# Power.net
KiCad netlist of a schematic drawn in Altium Designer
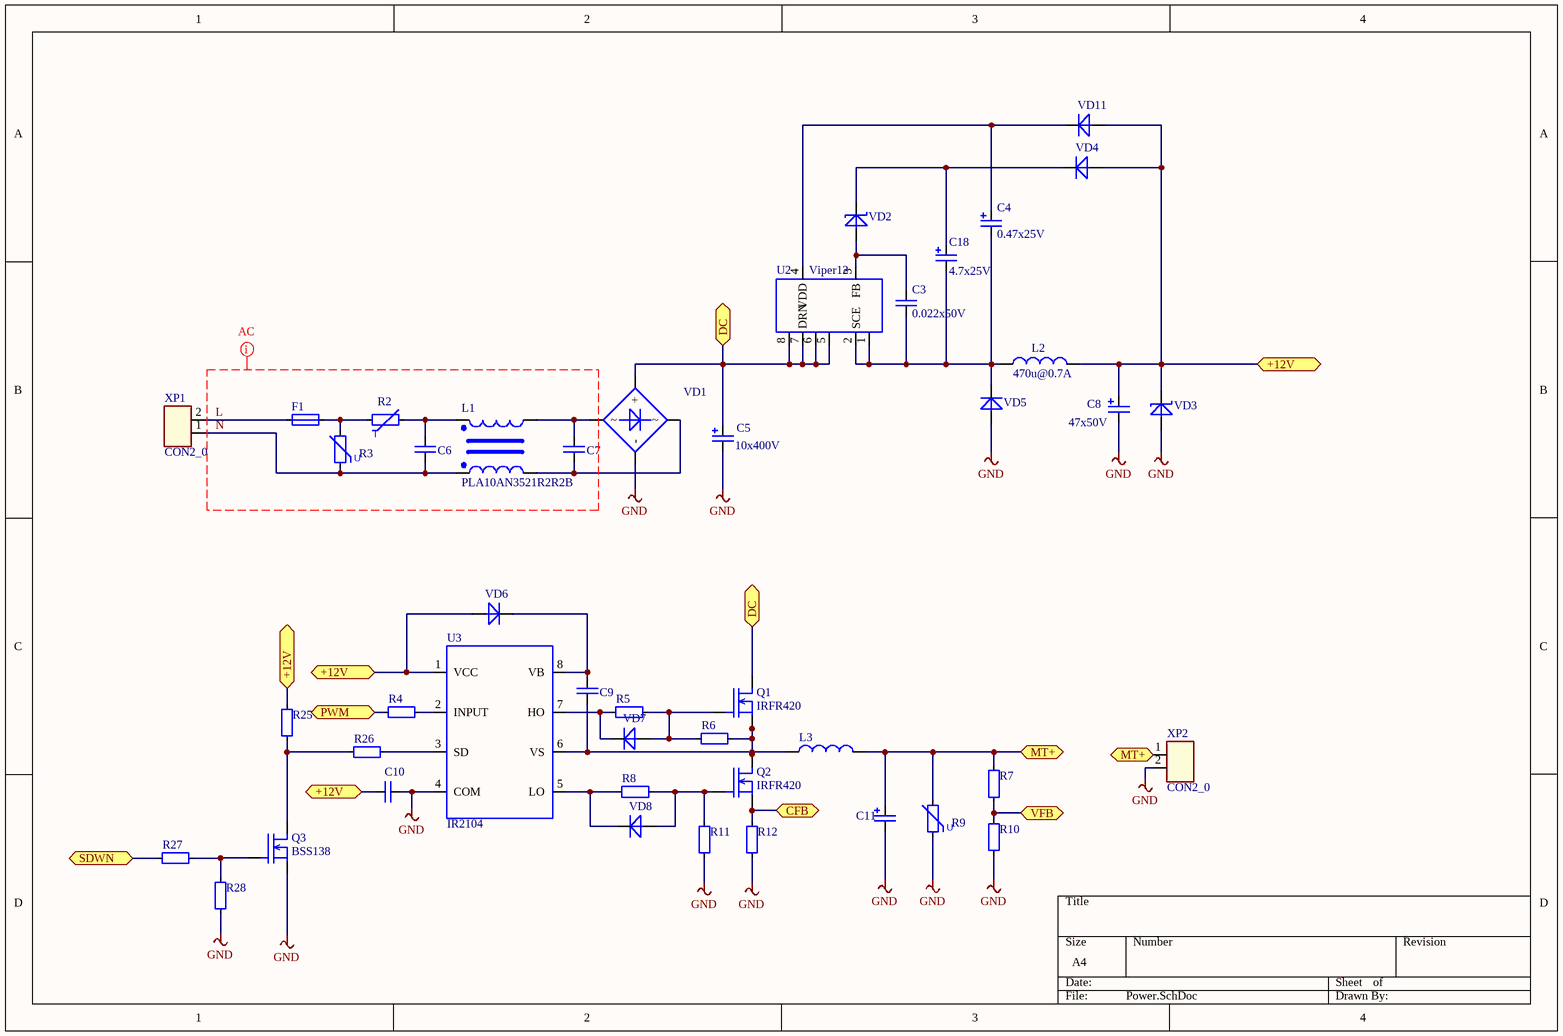
[diagram p0: Power.SchDoc]

(export (version "E")
  (design (tool "Eeschema 10.0.6"))
  (components
    (comp (ref "C3")
      (value "0.022x50V")
      (footprint "DISCRETE:SMD_0805")
      (description "None polar capacitor")
      (libsource (lib "DISCRETE") (part "C_NONE_POLAR"))
    )
    (comp (ref "C4")
      (value "0.47x25V")
      (footprint "DISCRETE:CAPR-5/2.5")
      (description "Polar capacitor")
      (libsource (lib "DISCRETE") (part "C_POLAR"))
    )
    (comp (ref "C5")
      (value "10x400V")
      (footprint "DISCRETE:CAPR-10/5")
      (description "Polar capacitor")
      (libsource (lib "DISCRETE") (part "C_POLAR"))
    )
    (comp (ref "C6")
      (value "~")
      (footprint "DISCRETE:MKR-X2-0.22-10")
      (description "None polar capacitor")
      (libsource (lib "DISCRETE") (part "C_NONE_POLAR"))
    )
    (comp (ref "C7")
      (value "~")
      (footprint "DISCRETE:MKR-X2-0.22-10")
      (description "None polar capacitor")
      (libsource (lib "DISCRETE") (part "C_NONE_POLAR"))
    )
    (comp (ref "C8")
      (value "47x50V")
      (footprint "DISCRETE:CAPR-5/2.5")
      (description "Polar capacitor")
      (libsource (lib "DISCRETE") (part "C_POLAR"))
    )
    (comp (ref "C9")
      (value "~")
      (footprint "DISCRETE:SMD_0805")
      (description "None polar capacitor")
      (libsource (lib "DISCRETE") (part "C_NONE_POLAR"))
    )
    (comp (ref "C10")
      (value "~")
      (footprint "DISCRETE:SMD_0805")
      (description "None polar capacitor")
      (libsource (lib "DISCRETE") (part "C_NONE_POLAR"))
    )
    (comp (ref "C11")
      (value "~")
      (footprint "DISCRETE:CAPR-5/2.5")
      (description "Polar capacitor")
      (libsource (lib "DISCRETE") (part "C_POLAR"))
    )
    (comp (ref "C18")
      (value "4.7x25V")
      (footprint "DISCRETE:CAPR-5/2.5")
      (description "Polar capacitor")
      (libsource (lib "DISCRETE") (part "C_POLAR"))
    )
    (comp (ref "F1")
      (value "~")
      (footprint "DISCRETE:KLS-1009")
      (description "Resistor")
      (libsource (lib "DISCRETE") (part "FUSE"))
    )
    (comp (ref "L1")
      (value "PLA10AN3521R2R2B")
      (footprint "DISCRETE:PLA10AN3521R2R2B")
      (libsource (lib "DISCRETE") (part "Inductor Sin"))
    )
    (comp (ref "L2")
      (value "470u@0.7A")
      (footprint "DISCRETE:IND-DV0470.00K")
      (libsource (lib "DISCRETE") (part "INDUCTOR"))
    )
    (comp (ref "L3")
      (value "~")
      (footprint "DISCRETE:IND-DV0470.00K")
      (libsource (lib "DISCRETE") (part "INDUCTOR"))
    )
    (comp (ref "Q1")
      (value "IRFR420")
      (footprint "DISCRETE:TO-252")
      (description "IG-FET N-Channel")
      (libsource (lib "Transistors") (part "IRFR420"))
    )
    (comp (ref "Q2")
      (value "IRFR420")
      (footprint "DISCRETE:TO-252")
      (description "IG-FET N-Channel")
      (libsource (lib "Transistors") (part "IRFR420"))
    )
    (comp (ref "Q3")
      (value "BSS138")
      (footprint "DISCRETE:SOT23-3PIN")
      (description "IG-FET N-Channel")
      (libsource (lib "Transistors") (part "BSS138"))
    )
    (comp (ref "R2")
      (value "RES NTC")
      (footprint "DISCRETE:NTC-5mm")
      (libsource (lib "DISCRETE") (part "RES NTC"))
    )
    (comp (ref "R3")
      (value "RES VARISTOR")
      (footprint "DISCRETE:VAR-10D")
      (libsource (lib "DISCRETE") (part "RES VARISTOR"))
    )
    (comp (ref "R4")
      (value "~")
      (footprint "DISCRETE:SMD_0805")
      (description "Resistor")
      (libsource (lib "DISCRETE") (part "RES"))
    )
    (comp (ref "R5")
      (value "~")
      (footprint "DISCRETE:SMD_0805")
      (description "Resistor")
      (libsource (lib "") (part "RES_2"))
    )
    (comp (ref "R6")
      (value "~")
      (footprint "DISCRETE:SMD_0805")
      (description "Resistor")
      (libsource (lib "DISCRETE") (part "RES"))
    )
    (comp (ref "R7")
      (value "~")
      (footprint "DISCRETE:SMD_0805")
      (description "Resistor")
      (libsource (lib "") (part "RES_3"))
    )
    (comp (ref "R8")
      (value "~")
      (footprint "DISCRETE:SMD_0805")
      (description "Resistor")
      (libsource (lib "") (part "RES_2"))
    )
    (comp (ref "R9")
      (value "RES VARISTOR")
      (footprint "DISCRETE:VAR-05D")
      (libsource (lib "DISCRETE") (part "RES VARISTOR"))
    )
    (comp (ref "R10")
      (value "~")
      (footprint "DISCRETE:SMD_0805")
      (description "Resistor")
      (libsource (lib "") (part "RES_3"))
    )
    (comp (ref "R11")
      (value "~")
      (footprint "DISCRETE:SMD_0805")
      (description "Resistor")
      (libsource (lib "") (part "RES_1"))
    )
    (comp (ref "R12")
      (value "~")
      (footprint "DISCRETE:SMD_0805")
      (description "Resistor")
      (libsource (lib "") (part "RES_1"))
    )
    (comp (ref "R25")
      (value "~")
      (footprint "DISCRETE:SMD_0805")
      (description "Resistor")
      (libsource (lib "") (part "RES_3"))
    )
    (comp (ref "R26")
      (value "~")
      (footprint "DISCRETE:SMD_0805")
      (description "Resistor")
      (libsource (lib "DISCRETE") (part "RES"))
    )
    (comp (ref "R27")
      (value "~")
      (footprint "DISCRETE:SMD_0805")
      (description "Resistor")
      (libsource (lib "") (part "RES_2"))
    )
    (comp (ref "R28")
      (value "~")
      (footprint "DISCRETE:SMD_0805")
      (description "Resistor")
      (libsource (lib "") (part "RES_3"))
    )
    (comp (ref "U2")
      (value "Viper12")
      (footprint "ICs:SO8-150mil")
      (description "Step-Down Converter")
      (fields (field (name "MANUFACTURER") "STMicro"))
      (libsource (lib "ICs") (part "Viper12"))
    )
    (comp (ref "U3") (value "IR2104") (footprint "ICs:SO8-150mil") (libsource (lib "ICs") (part "IR2104")))
    (comp (ref "VD1")
      (value "DIODE BRIDGE")
      (footprint "DISCRETE:GBU BRIDGE")
      (libsource (lib "DISCRETE") (part "DIODE BRIDGE"))
    )
    (comp (ref "VD2")
      (value "~")
      (footprint "DISCRETE:SOD-123")
      (description "Zener diode")
      (libsource (lib "DISCRETE") (part "ZENER"))
    )
    (comp (ref "VD3")
      (value "~")
      (footprint "DISCRETE:SOD-123")
      (description "Zener diode")
      (libsource (lib "DISCRETE") (part "ZENER"))
    )
    (comp (ref "VD4")
      (value "~")
      (footprint "DISCRETE:DO214-AC")
      (description "Diode")
      (libsource (lib "DISCRETE") (part "DIODE"))
    )
    (comp (ref "VD5")
      (value "~")
      (footprint "DISCRETE:DO214-AC")
      (description "Diode")
      (libsource (lib "DISCRETE") (part "DIODE"))
    )
    (comp (ref "VD6")
      (value "~")
      (footprint "DISCRETE:DO214-AC")
      (description "Diode")
      (libsource (lib "DISCRETE") (part "DIODE"))
    )
    (comp (ref "VD7")
      (value "~")
      (footprint "DISCRETE:DIO-MELF_SOD-80")
      (description "Diode")
      (libsource (lib "DISCRETE") (part "DIODE"))
    )
    (comp (ref "VD8")
      (value "~")
      (footprint "DISCRETE:DIO-MELF_SOD-80")
      (description "Diode")
      (libsource (lib "DISCRETE") (part "DIODE"))
    )
    (comp (ref "VD11")
      (value "~")
      (footprint "DISCRETE:DO214-AC")
      (description "Diode")
      (libsource (lib "DISCRETE") (part "DIODE"))
    )
    (comp (ref "XP1")
      (value "CON2_0")
      (footprint "Connectors:SCREW_TERM-5.0/2")
      (libsource (lib "Connectors") (part "CON2_0"))
    )
    (comp (ref "XP2")
      (value "CON2_0")
      (footprint "Connectors:SCREW_TERM-5.0/2")
      (libsource (lib "") (part "CON2_0_1"))
    )
  )
  (nets
    (net (code "1") (name "/+12V") (class "Default")
      (node (ref "C10") (pin "1") (pintype "passive"))
      (node (ref "C8") (pin "1") (pintype "passive"))
      (node (ref "L2") (pin "2") (pinfunction "2_2") (pintype "passive"))
      (node (ref "R25") (pin "2") (pintype "passive"))
      (node (ref "U3") (pin "1") (pinfunction "VCC_1") (pintype "passive"))
      (node (ref "VD11") (pin "2") (pinfunction "A_2") (pintype "passive"))
      (node (ref "VD3") (pin "1") (pinfunction "C_1") (pintype "passive"))
      (node (ref "VD4") (pin "2") (pinfunction "A_2") (pintype "passive"))
      (node (ref "VD6") (pin "2") (pinfunction "A_2") (pintype "passive"))
    )
    (net (code "2") (name "/CFB") (class "Default")
      (node (ref "Q2") (pin "3") (pinfunction "D_3") (pintype "passive"))
      (node (ref "R12") (pin "1") (pintype "passive"))
    )
    (net (code "3") (name "/DC") (class "Default")
      (node (ref "C5") (pin "1") (pintype "passive"))
      (node (ref "Q1") (pin "2") (pinfunction "S_2") (pintype "passive"))
      (node (ref "U2") (pin "5") (pinfunction "DRN_5") (pintype "passive"))
      (node (ref "U2") (pin "6") (pinfunction "DRN_6") (pintype "passive"))
      (node (ref "U2") (pin "7") (pinfunction "DRN_7") (pintype "passive"))
      (node (ref "U2") (pin "8") (pinfunction "DRN_8") (pintype "passive"))
      (node (ref "VD1") (pin "1") (pinfunction "+_1") (pintype "passive"))
    )
    (net (code "4") (name "/L") (class "Default")
      (node (ref "F1") (pin "2") (pintype "passive"))
      (node (ref "XP1") (pin "2") (pinfunction "2_2") (pintype "passive"))
    )
    (net (code "5") (name "/MT+") (class "Default")
      (node (ref "C11") (pin "1") (pintype "passive"))
      (node (ref "L3") (pin "2") (pinfunction "2_2") (pintype "passive"))
      (node (ref "R7") (pin "2") (pintype "passive"))
      (node (ref "R9") (pin "2") (pintype "passive"))
      (node (ref "XP2") (pin "1") (pinfunction "1_1") (pintype "passive"))
    )
    (net (code "6") (name "/N") (class "Default")
      (node (ref "C6") (pin "2") (pintype "passive"))
      (node (ref "L1") (pin "1") (pinfunction "1_1") (pintype "passive"))
      (node (ref "R3") (pin "1") (pintype "passive"))
      (node (ref "XP1") (pin "1") (pinfunction "1_1") (pintype "passive"))
    )
    (net (code "7") (name "/PWM") (class "Default") (node (ref "R4") (pin "1") (pintype "passive")))
    (net (code "8") (name "/SDWN") (class "Default") (node (ref "R27") (pin "2") (pintype "passive")))
    (net (code "9") (name "/VFB") (class "Default")
      (node (ref "R10") (pin "2") (pintype "passive"))
      (node (ref "R7") (pin "1") (pintype "passive"))
    )
    (net (code "10") (name "GND") (class "Default")
      (node (ref "C10") (pin "2") (pintype "passive"))
      (node (ref "C11") (pin "2") (pintype "passive"))
      (node (ref "C5") (pin "2") (pintype "passive"))
      (node (ref "C8") (pin "2") (pintype "passive"))
      (node (ref "Q3") (pin "2") (pinfunction "S_2") (pintype "passive"))
      (node (ref "R10") (pin "1") (pintype "passive"))
      (node (ref "R11") (pin "2") (pintype "passive"))
      (node (ref "R12") (pin "2") (pintype "passive"))
      (node (ref "R28") (pin "1") (pintype "passive"))
      (node (ref "R9") (pin "1") (pintype "passive"))
      (node (ref "U3") (pin "4") (pinfunction "COM_4") (pintype "passive"))
      (node (ref "VD1") (pin "4") (pinfunction "-_4") (pintype "passive"))
      (node (ref "VD3") (pin "2") (pinfunction "A_2") (pintype "passive"))
      (node (ref "VD5") (pin "2") (pinfunction "A_2") (pintype "passive"))
      (node (ref "XP2") (pin "2") (pinfunction "2_2") (pintype "passive"))
    )
    (net (code "11") (name "Net-(C6-Pad1)") (class "Default")
      (node (ref "C6") (pin "1") (pintype "passive"))
      (node (ref "L1") (pin "4") (pinfunction "4_4") (pintype "passive"))
      (node (ref "R2") (pin "2") (pintype "passive"))
    )
    (net (code "12") (name "Net-(C7-Pad1)") (class "Default")
      (node (ref "C7") (pin "1") (pintype "passive"))
      (node (ref "L1") (pin "3") (pinfunction "3_3") (pintype "passive"))
      (node (ref "VD1") (pin "2") (pinfunction "~_2") (pintype "passive"))
    )
    (net (code "13") (name "Net-(C7-Pad2)") (class "Default")
      (node (ref "C7") (pin "2") (pintype "passive"))
      (node (ref "L1") (pin "2") (pinfunction "2_2") (pintype "passive"))
      (node (ref "VD1") (pin "3") (pinfunction "~_3") (pintype "passive"))
    )
    (net (code "14") (name "Net-(F1-Pad1)") (class "Default")
      (node (ref "F1") (pin "1") (pintype "passive"))
      (node (ref "R2") (pin "1") (pintype "passive"))
      (node (ref "R3") (pin "2") (pintype "passive"))
    )
    (net (code "15") (name "Net-(Q1-D)") (class "Default")
      (node (ref "C9") (pin "2") (pintype "passive"))
      (node (ref "L3") (pin "1") (pinfunction "1_1") (pintype "passive"))
      (node (ref "Q1") (pin "3") (pinfunction "D_3") (pintype "passive"))
      (node (ref "Q2") (pin "2") (pinfunction "S_2") (pintype "passive"))
      (node (ref "R6") (pin "2") (pintype "passive"))
      (node (ref "U3") (pin "6") (pinfunction "VS_6") (pintype "passive"))
    )
    (net (code "16") (name "Net-(Q1-G)") (class "Default")
      (node (ref "Q1") (pin "1") (pinfunction "G_1") (pintype "passive"))
      (node (ref "R5") (pin "1") (pintype "passive"))
      (node (ref "R6") (pin "1") (pintype "passive"))
      (node (ref "VD7") (pin "2") (pinfunction "A_2") (pintype "passive"))
    )
    (net (code "17") (name "Net-(Q2-G)") (class "Default")
      (node (ref "Q2") (pin "1") (pinfunction "G_1") (pintype "passive"))
      (node (ref "R11") (pin "1") (pintype "passive"))
      (node (ref "R8") (pin "1") (pintype "passive"))
      (node (ref "VD8") (pin "2") (pinfunction "A_2") (pintype "passive"))
    )
    (net (code "18") (name "Net-(Q3-D)") (class "Default")
      (node (ref "Q3") (pin "3") (pinfunction "D_3") (pintype "passive"))
      (node (ref "R25") (pin "1") (pintype "passive"))
      (node (ref "R26") (pin "1") (pintype "passive"))
    )
    (net (code "19") (name "Net-(Q3-G)") (class "Default")
      (node (ref "Q3") (pin "1") (pinfunction "G_1") (pintype "passive"))
      (node (ref "R27") (pin "1") (pintype "passive"))
      (node (ref "R28") (pin "2") (pintype "passive"))
    )
    (net (code "20") (name "Net-(U2-FB)") (class "Default")
      (node (ref "C3") (pin "1") (pintype "passive"))
      (node (ref "U2") (pin "3") (pinfunction "FB_3") (pintype "passive"))
      (node (ref "VD2") (pin "2") (pinfunction "A_2") (pintype "passive"))
    )
    (net (code "21") (name "Net-(U2-VDD)") (class "Default")
      (node (ref "C4") (pin "1") (pintype "passive"))
      (node (ref "U2") (pin "4") (pinfunction "VDD_4") (pintype "passive"))
      (node (ref "VD11") (pin "1") (pinfunction "C_1") (pintype "passive"))
    )
    (net (code "22") (name "Net-(U3-HO)") (class "Default")
      (node (ref "R5") (pin "2") (pintype "passive"))
      (node (ref "U3") (pin "7") (pinfunction "HO_7") (pintype "passive"))
      (node (ref "VD7") (pin "1") (pinfunction "C_1") (pintype "passive"))
    )
    (net (code "23") (name "Net-(U3-INPUT)") (class "Default")
      (node (ref "R4") (pin "2") (pintype "passive"))
      (node (ref "U3") (pin "2") (pinfunction "INPUT_2") (pintype "passive"))
    )
    (net (code "24") (name "Net-(U3-LO)") (class "Default")
      (node (ref "R8") (pin "2") (pintype "passive"))
      (node (ref "U3") (pin "5") (pinfunction "LO_5") (pintype "passive"))
      (node (ref "VD8") (pin "1") (pinfunction "C_1") (pintype "passive"))
    )
    (net (code "25") (name "Net-(U3-SD)") (class "Default")
      (node (ref "R26") (pin "2") (pintype "passive"))
      (node (ref "U3") (pin "3") (pinfunction "SD_3") (pintype "passive"))
    )
    (net (code "26") (name "Net-(U3-VB)") (class "Default")
      (node (ref "C9") (pin "1") (pintype "passive"))
      (node (ref "U3") (pin "8") (pinfunction "VB_8") (pintype "passive"))
      (node (ref "VD6") (pin "1") (pinfunction "C_1") (pintype "passive"))
    )
    (net (code "27") (name "Net-(VD2-C)") (class "Default")
      (node (ref "C18") (pin "1") (pintype "passive"))
      (node (ref "VD2") (pin "1") (pinfunction "C_1") (pintype "passive"))
      (node (ref "VD4") (pin "1") (pinfunction "C_1") (pintype "passive"))
    )
    (net (code "28") (name "Net-(VD5-C)") (class "Default")
      (node (ref "C18") (pin "2") (pintype "passive"))
      (node (ref "C3") (pin "2") (pintype "passive"))
      (node (ref "C4") (pin "2") (pintype "passive"))
      (node (ref "L2") (pin "1") (pinfunction "1_1") (pintype "passive"))
      (node (ref "U2") (pin "1") (pinfunction "SCE_1") (pintype "passive"))
      (node (ref "U2") (pin "2") (pinfunction "SCE_2") (pintype "passive"))
      (node (ref "VD5") (pin "1") (pinfunction "C_1") (pintype "passive"))
    )
  )
)
